# MainFile.net
KiCad netlist of a schematic drawn in Altium Designer
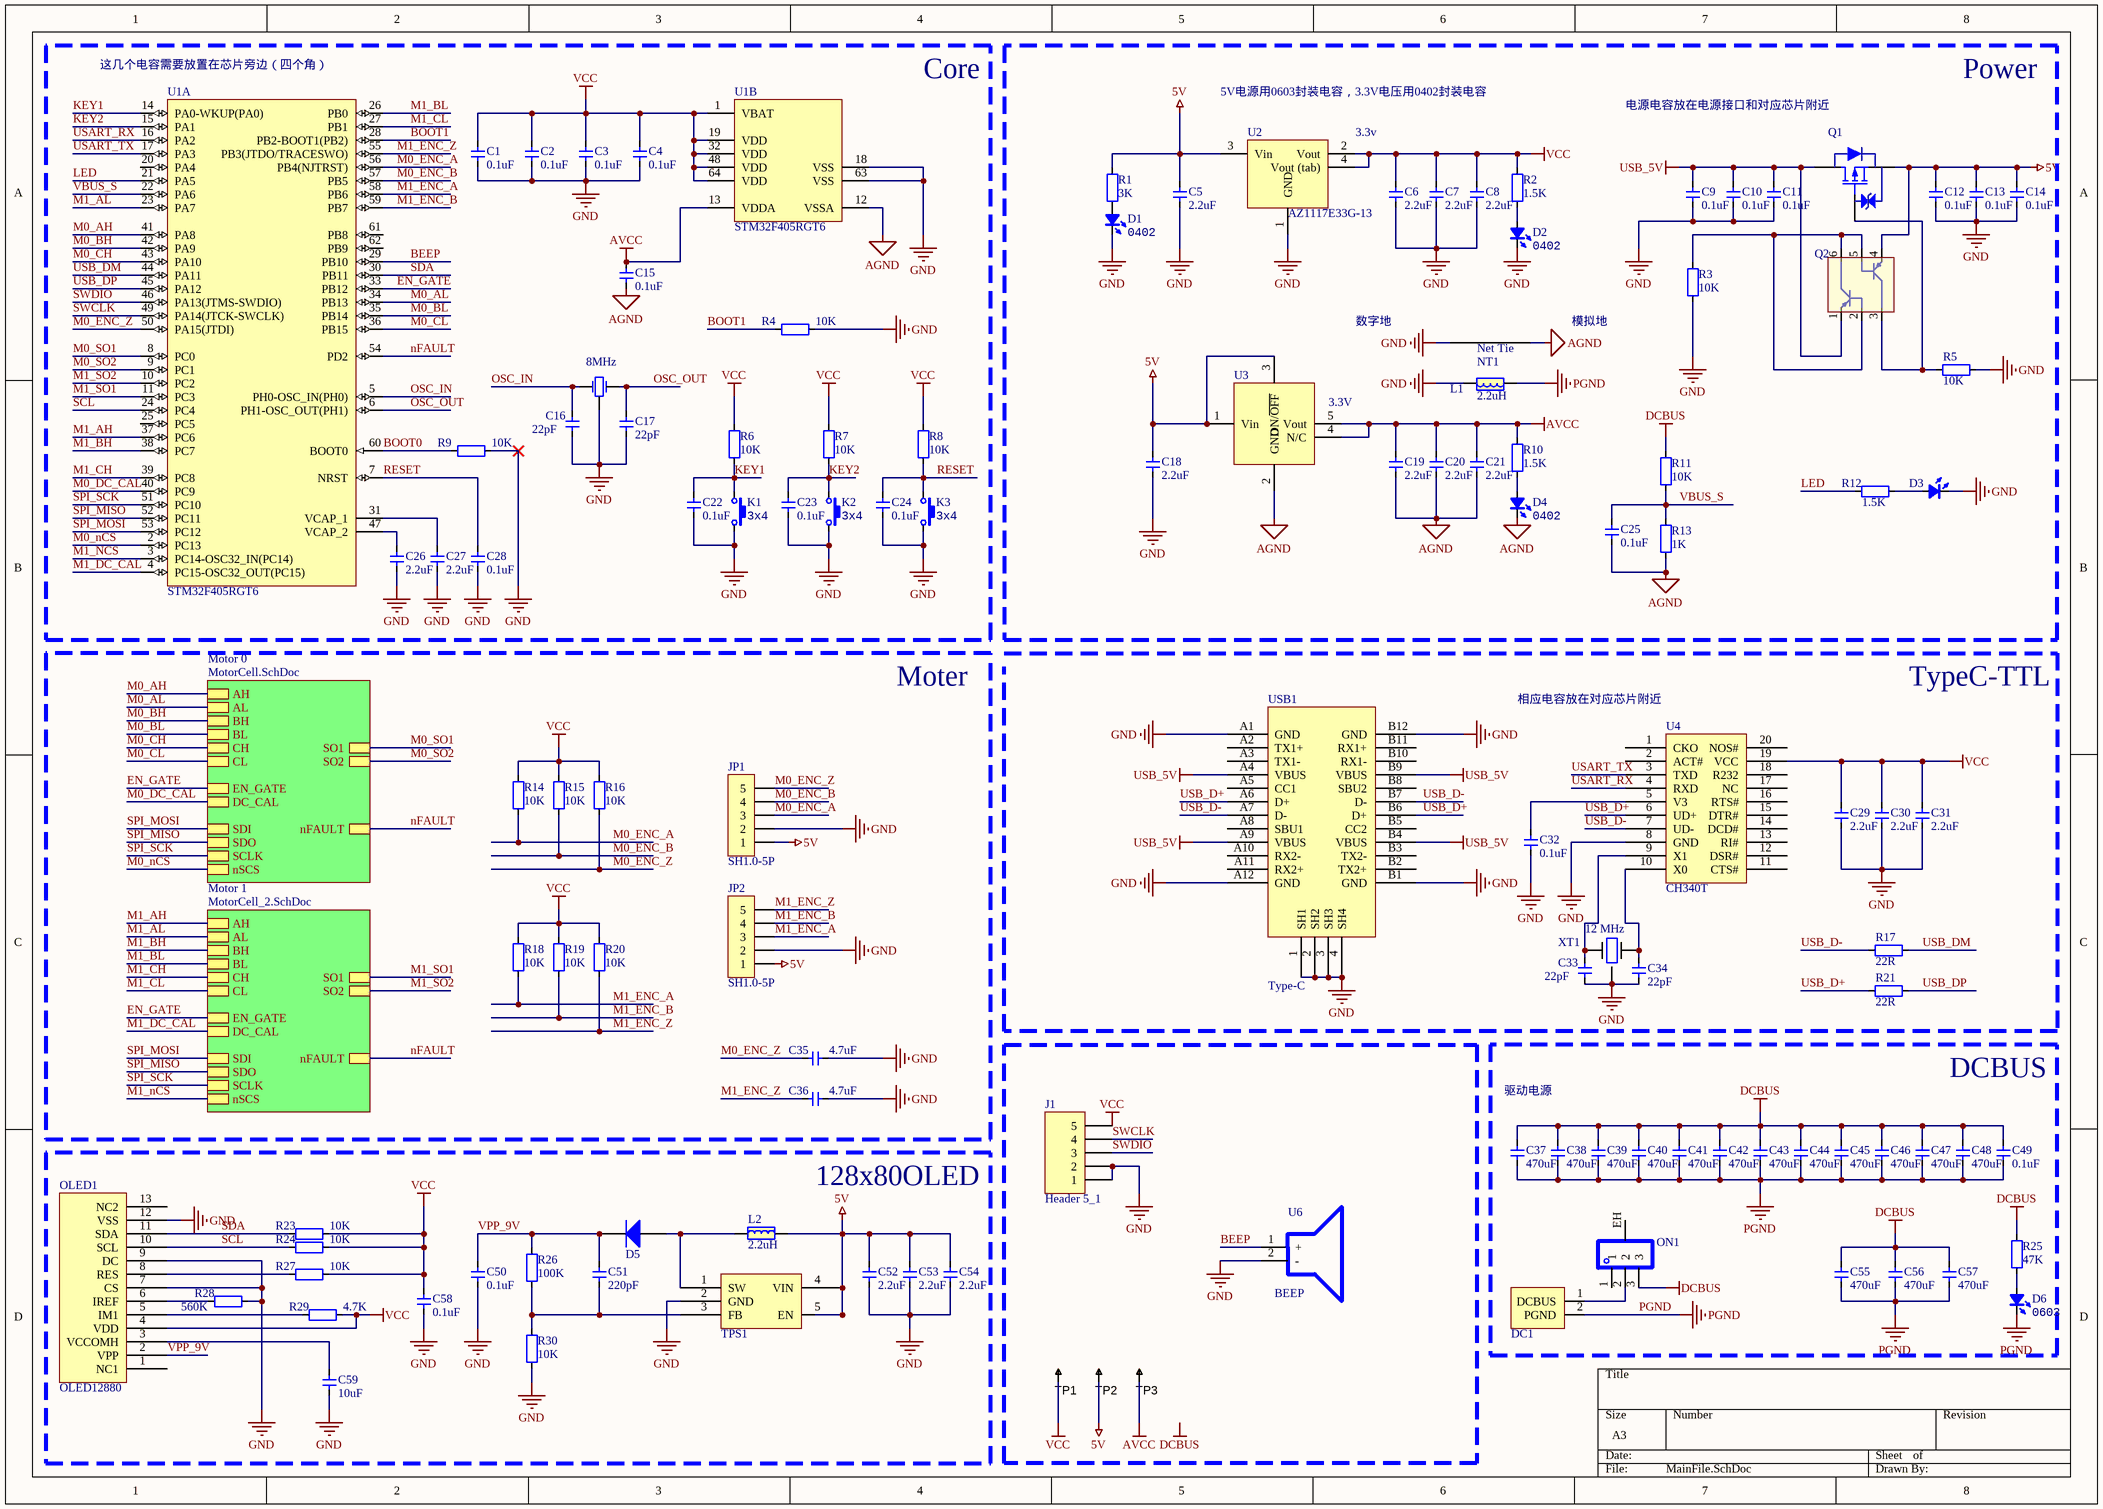
[diagram p0: MainFile.SchDoc]

(export (version "E")
  (design (tool "Eeschema 10.0.6"))
  (components
    (comp (ref "C1")
      (value "0.1uF")
      (footprint "CAP_0402")
      (description "Capacitor")
      (libsource (lib "VectorController") (part "电容-0402"))
    )
    (comp (ref "C2")
      (value "0.1uF")
      (footprint "CAP_0402")
      (description "Capacitor")
      (libsource (lib "VectorController") (part "电容-0402"))
    )
    (comp (ref "C3")
      (value "0.1uF")
      (footprint "CAP_0402")
      (description "Capacitor")
      (libsource (lib "VectorController") (part "电容-0402"))
    )
    (comp (ref "C4")
      (value "0.1uF")
      (footprint "CAP_0402")
      (description "Capacitor")
      (libsource (lib "VectorController") (part "电容-0402"))
    )
    (comp (ref "C5")
      (value "2.2uF")
      (footprint "CAP_0603")
      (description "Capacitor")
      (libsource (lib "Ctrl_FOC") (part "电容-0603"))
    )
    (comp (ref "C6")
      (value "2.2uF")
      (footprint "CAP_0402")
      (description "Capacitor")
      (libsource (lib "Ctrl_FOC") (part "电容-0402"))
    )
    (comp (ref "C7")
      (value "2.2uF")
      (footprint "CAP_0402")
      (description "Capacitor")
      (libsource (lib "Ctrl_FOC") (part "电容-0402"))
    )
    (comp (ref "C8")
      (value "2.2uF")
      (footprint "CAP_0402")
      (description "Capacitor")
      (libsource (lib "Ctrl_FOC") (part "电容-0402"))
    )
    (comp (ref "C9")
      (value "0.1uF")
      (footprint "CAP_0603")
      (description "Capacitor")
      (libsource (lib "Ctrl_FOC") (part "电容-0603"))
    )
    (comp (ref "C10")
      (value "0.1uF")
      (footprint "CAP_0603")
      (description "Capacitor")
      (libsource (lib "Ctrl_FOC") (part "电容-0603"))
    )
    (comp (ref "C11")
      (value "0.1uF")
      (footprint "CAP_0603")
      (description "Capacitor")
      (libsource (lib "Ctrl_FOC") (part "电容-0603"))
    )
    (comp (ref "C12")
      (value "0.1uF")
      (footprint "CAP_0603")
      (description "Capacitor")
      (libsource (lib "Ctrl_FOC") (part "电容-0603"))
    )
    (comp (ref "C13")
      (value "0.1uF")
      (footprint "CAP_0603")
      (description "Capacitor")
      (libsource (lib "Ctrl_FOC") (part "电容-0603"))
    )
    (comp (ref "C14")
      (value "0.1uF")
      (footprint "CAP_0603")
      (description "Capacitor")
      (libsource (lib "Ctrl_FOC") (part "电容-0603"))
    )
    (comp (ref "C15")
      (value "0.1uF")
      (footprint "CAP_0603")
      (description "Capacitor")
      (libsource (lib "Ctrl_FOC") (part "电容-0603"))
    )
    (comp (ref "C16")
      (value "22pF")
      (footprint "CAP_0402")
      (description "Capacitor")
      (libsource (lib "Ctrl_FOC") (part "电容-0402"))
    )
    (comp (ref "C17")
      (value "22pF")
      (footprint "CAP_0402")
      (description "Capacitor")
      (libsource (lib "Ctrl_FOC") (part "电容-0402"))
    )
    (comp (ref "C18")
      (value "2.2uF")
      (footprint "CAP_0603")
      (description "Capacitor")
      (libsource (lib "Ctrl_FOC") (part "电容-0603"))
    )
    (comp (ref "C19")
      (value "2.2uF")
      (footprint "CAP_0402")
      (description "Capacitor")
      (libsource (lib "Ctrl_FOC") (part "电容-0402"))
    )
    (comp (ref "C20")
      (value "2.2uF")
      (footprint "CAP_0402")
      (description "Capacitor")
      (libsource (lib "Ctrl_FOC") (part "电容-0402"))
    )
    (comp (ref "C21")
      (value "2.2uF")
      (footprint "CAP_0402")
      (description "Capacitor")
      (libsource (lib "Ctrl_FOC") (part "电容-0402"))
    )
    (comp (ref "C22")
      (value "0.1uF")
      (footprint "CAP_0402")
      (description "Capacitor")
      (libsource (lib "VectorController") (part "电容-0402"))
    )
    (comp (ref "C23")
      (value "0.1uF")
      (footprint "CAP_0402")
      (description "Capacitor")
      (libsource (lib "VectorController") (part "电容-0402"))
    )
    (comp (ref "C24")
      (value "0.1uF")
      (footprint "CAP_0402")
      (description "Capacitor")
      (libsource (lib "VectorController") (part "电容-0402"))
    )
    (comp (ref "C25")
      (value "0.1uF")
      (footprint "CAP_0603")
      (description "Capacitor")
      (libsource (lib "Ctrl_FOC") (part "电容-0603"))
    )
    (comp (ref "C26")
      (value "2.2uF")
      (footprint "CAP_0402")
      (description "Capacitor")
      (libsource (lib "Ctrl_FOC") (part "电容-0402"))
    )
    (comp (ref "C27")
      (value "2.2uF")
      (footprint "CAP_0402")
      (description "Capacitor")
      (libsource (lib "Ctrl_FOC") (part "电容-0402"))
    )
    (comp (ref "C28")
      (value "0.1uF")
      (footprint "CAP_0402")
      (description "Capacitor")
      (libsource (lib "Ctrl_FOC") (part "电容-0402"))
    )
    (comp (ref "C29")
      (value "2.2uF")
      (footprint "CAP_0603")
      (description "Capacitor")
      (libsource (lib "Ctrl_FOC") (part "电容-0603"))
    )
    (comp (ref "C30")
      (value "2.2uF")
      (footprint "CAP_0603")
      (description "Capacitor")
      (libsource (lib "Ctrl_FOC") (part "电容-0603"))
    )
    (comp (ref "C31")
      (value "2.2uF")
      (footprint "CAP_0603")
      (description "Capacitor")
      (libsource (lib "Ctrl_FOC") (part "电容-0603"))
    )
    (comp (ref "C32")
      (value "0.1uF")
      (footprint "CAP_0402")
      (description "Capacitor")
      (libsource (lib "Ctrl_FOC") (part "电容-0402"))
    )
    (comp (ref "C33")
      (value "22pF")
      (footprint "CAP_0402")
      (description "Capacitor")
      (libsource (lib "Ctrl_FOC") (part "电容-0402"))
    )
    (comp (ref "C34")
      (value "22pF")
      (footprint "CAP_0402")
      (description "Capacitor")
      (libsource (lib "Ctrl_FOC") (part "电容-0402"))
    )
    (comp (ref "C35")
      (value "4.7uF")
      (footprint "CAP_0402")
      (description "Capacitor")
      (libsource (lib "VectorController") (part "电容-0402"))
    )
    (comp (ref "C36")
      (value "4.7uF")
      (footprint "CAP_0402")
      (description "Capacitor")
      (libsource (lib "VectorController") (part "电容-0402"))
    )
    (comp (ref "C37")
      (value "470uF")
      (footprint "CAP_1206")
      (description "Capacitor")
      (libsource (lib "Ctrl_FOC") (part "电容-1206"))
    )
    (comp (ref "C38")
      (value "470uF")
      (footprint "CAP_1206")
      (description "Capacitor")
      (libsource (lib "Ctrl_FOC") (part "电容-1206"))
    )
    (comp (ref "C39")
      (value "470uF")
      (footprint "CAP_1206")
      (description "Capacitor")
      (libsource (lib "Ctrl_FOC") (part "电容-1206"))
    )
    (comp (ref "C40")
      (value "470uF")
      (footprint "CAP_1206")
      (description "Capacitor")
      (libsource (lib "Ctrl_FOC") (part "电容-1206"))
    )
    (comp (ref "C41")
      (value "470uF")
      (footprint "CAP_1206")
      (description "Capacitor")
      (libsource (lib "Ctrl_FOC") (part "电容-1206"))
    )
    (comp (ref "C42")
      (value "470uF")
      (footprint "CAP_1206")
      (description "Capacitor")
      (libsource (lib "Ctrl_FOC") (part "电容-1206"))
    )
    (comp (ref "C43")
      (value "470uF")
      (footprint "CAP_1206")
      (description "Capacitor")
      (libsource (lib "Ctrl_FOC") (part "电容-1206"))
    )
    (comp (ref "C44")
      (value "470uF")
      (footprint "CAP_1206")
      (description "Capacitor")
      (libsource (lib "Ctrl_FOC") (part "电容-1206"))
    )
    (comp (ref "C45")
      (value "470uF")
      (footprint "CAP_1206")
      (description "Capacitor")
      (libsource (lib "Ctrl_FOC") (part "电容-1206"))
    )
    (comp (ref "C46")
      (value "470uF")
      (footprint "CAP_1206")
      (description "Capacitor")
      (libsource (lib "Ctrl_FOC") (part "电容-1206"))
    )
    (comp (ref "C47")
      (value "470uF")
      (footprint "CAP_1206")
      (description "Capacitor")
      (libsource (lib "Ctrl_FOC") (part "电容-1206"))
    )
    (comp (ref "C48")
      (value "470uF")
      (footprint "CAP_1206")
      (description "Capacitor")
      (libsource (lib "Ctrl_FOC") (part "电容-1206"))
    )
    (comp (ref "C49")
      (value "0.1uF")
      (footprint "CAP_1206")
      (description "Capacitor")
      (libsource (lib "Ctrl_FOC") (part "电容-1206"))
    )
    (comp (ref "C50")
      (value "0.1uF")
      (footprint "CAP_0402")
      (description "Capacitor")
      (libsource (lib "VectorController") (part "电容-0402"))
    )
    (comp (ref "C51")
      (value "220pF")
      (footprint "CAP_0402")
      (description "Capacitor")
      (libsource (lib "VectorController") (part "电容-0402"))
    )
    (comp (ref "C52")
      (value "2.2uF")
      (footprint "CAP_0603")
      (description "Capacitor")
      (libsource (lib "Ctrl_FOC") (part "电容-0603"))
    )
    (comp (ref "C53")
      (value "2.2uF")
      (footprint "CAP_0603")
      (description "Capacitor")
      (libsource (lib "Ctrl_FOC") (part "电容-0603"))
    )
    (comp (ref "C54")
      (value "2.2uF")
      (footprint "CAP_0603")
      (description "Capacitor")
      (libsource (lib "Ctrl_FOC") (part "电容-0603"))
    )
    (comp (ref "C55")
      (value "470uF")
      (footprint "CAP_1206")
      (description "Capacitor")
      (libsource (lib "Ctrl_FOC") (part "电容-1206"))
    )
    (comp (ref "C56")
      (value "470uF")
      (footprint "CAP_1206")
      (description "Capacitor")
      (libsource (lib "Ctrl_FOC") (part "电容-1206"))
    )
    (comp (ref "C57")
      (value "470uF")
      (footprint "CAP_1206")
      (description "Capacitor")
      (libsource (lib "Ctrl_FOC") (part "电容-1206"))
    )
    (comp (ref "C58")
      (value "0.1uF")
      (footprint "CAP_0402")
      (description "Capacitor")
      (libsource (lib "VectorController") (part "电容-0402"))
    )
    (comp (ref "C59")
      (value "10uF")
      (footprint "CAP_0402")
      (description "Capacitor")
      (libsource (lib "VectorController") (part "电容-0402"))
    )
    (comp (ref "D1")
      (value "color?")
      (footprint "LED_0402_BLUE")
      (description "LED")
      (fields (field (name "TYPE") "0402"))
      (libsource (lib "Ctrl_FOC") (part "LED_0402"))
    )
    (comp (ref "D2")
      (value "color?")
      (footprint "LED_0402_BLUE")
      (description "LED")
      (fields (field (name "TYPE") "0402"))
      (libsource (lib "Ctrl_FOC") (part "LED_0402"))
    )
    (comp (ref "D3")
      (value "color?")
      (footprint "LED_0402_BLUE")
      (description "LED")
      (libsource (lib "Vibration") (part "LED_0402"))
    )
    (comp (ref "D4")
      (value "color?")
      (footprint "LED_0402_BLUE")
      (description "LED")
      (fields (field (name "TYPE") "0402"))
      (libsource (lib "Ctrl_FOC") (part "LED_0402"))
    )
    (comp (ref "D5")
      (value "二极管-5819W")
      (footprint "SOD-123")
      (description "40V")
      (libsource (lib "VectorController") (part "二极管-5819W"))
    )
    (comp (ref "D6")
      (value "color?")
      (footprint "LED_0603")
      (description "LED")
      (fields (field (name "TYPE") "0603"))
      (libsource (lib "Ctrl_FOC") (part "LED_0603"))
    )
    (comp (ref "DC1")
      (value "电源")
      (footprint "TX60电源")
      (description "12~24VDC电源")
      (libsource (lib "Ctrl_FOC") (part "电源"))
    )
    (comp (ref "J1")
      (value "Header 5_1")
      (footprint "单排弯插针5")
      (description "Header, 5-Pin")
      (fields (field (name "PUBLISHER") "Altium Limited"))
      (libsource (lib "VectorController") (part "Header 5_1"))
    )
    (comp (ref "JP1")
      (value "SH1.0-5P")
      (footprint "SH1.0-5P-L")
      (description "5P接插件")
      (libsource (lib "VectorController") (part "Header 5"))
    )
    (comp (ref "JP2")
      (value "SH1.0-5P")
      (footprint "SH1.0-5P-L")
      (description "5P接插件")
      (libsource (lib "VectorController") (part "Header 5"))
    )
    (comp (ref "K1")
      (value "3x4")
      (footprint "按键_3x4x2")
      (description "Button")
      (fields (field (name "Comment") "TACT 2P"))
      (libsource (lib "Ctrl_FOC") (part "ButtonTACT_3x4x2_180"))
    )
    (comp (ref "K2")
      (value "3x4")
      (footprint "按键_3x4x2")
      (description "Button")
      (fields (field (name "Comment") "TACT 2P"))
      (libsource (lib "Ctrl_FOC") (part "ButtonTACT_3x4x2_180"))
    )
    (comp (ref "K3")
      (value "3x4")
      (footprint "按键_3x4x2")
      (description "Button")
      (fields (field (name "Comment") "TACT 2P"))
      (libsource (lib "Ctrl_FOC") (part "ButtonTACT_3x4x2_180"))
    )
    (comp (ref "L1")
      (value "2.2uH")
      (footprint "2520-L")
      (description "磁珠")
      (libsource (lib "VectorController") (part "电感-0805"))
    )
    (comp (ref "L2")
      (value "2.2uH")
      (footprint "2520-L")
      (description "磁珠")
      (libsource (lib "") (part "电感-0805_1"))
    )
    (comp (ref "NT1") (value "2mm") (footprint "NetTie_2mm") (libsource (lib "Ctrl_FOC") (part "NetTie_2mm")))
    (comp (ref "OLED1")
      (value "OLED12880")
      (footprint "OLED12880")
      (description "12880寸OLED")
      (libsource (lib "VectorController") (part "OLED12880"))
    )
    (comp (ref "ON1") (value "电源开关") (footprint "电源开关") (libsource (lib "Ctrl_FOC") (part "电源开关")))
    (comp (ref "Q1")
      (value "AO3415A")
      (footprint "SOT23-3")
      (description "MOSFET")
      (fields (field (name "PUBLISHER") "Altium Limited"))
      (libsource (lib "Ctrl_FOC") (part "AO3415A"))
    )
    (comp (ref "Q2")
      (value "BCM856BS")
      (footprint "SOT363-6")
      (description "Transistor")
      (libsource (lib "Ctrl_FOC") (part "BCM856BS"))
    )
    (comp (ref "R1")
      (value "3K")
      (footprint "RES_0603")
      (description "Resistor")
      (libsource (lib "Ctrl_FOC") (part "电阻-0603"))
    )
    (comp (ref "R2")
      (value "1.5K")
      (footprint "RES_0402")
      (description "Resistor")
      (libsource (lib "") (part "电阻-0402_2"))
    )
    (comp (ref "R3")
      (value "10K")
      (footprint "RES_0603")
      (description "Resistor")
      (libsource (lib "") (part "电阻-0603_3"))
    )
    (comp (ref "R4")
      (value "10K")
      (footprint "RES_0402")
      (description "Resistor")
      (libsource (lib "Ctrl_FOC") (part "电阻-0402"))
    )
    (comp (ref "R5")
      (value "10K")
      (footprint "RES_0603")
      (description "Resistor")
      (libsource (lib "") (part "电阻-0603_1"))
    )
    (comp (ref "R6")
      (value "10K")
      (footprint "RES_0402")
      (description "Resistor")
      (libsource (lib "") (part "电阻-0402_1"))
    )
    (comp (ref "R7")
      (value "10K")
      (footprint "RES_0402")
      (description "Resistor")
      (libsource (lib "") (part "电阻-0402_1"))
    )
    (comp (ref "R8")
      (value "10K")
      (footprint "RES_0402")
      (description "Resistor")
      (libsource (lib "") (part "电阻-0402_1"))
    )
    (comp (ref "R9")
      (value "10K")
      (footprint "RES_0402")
      (description "Resistor")
      (libsource (lib "Ctrl_FOC") (part "电阻-0402"))
    )
    (comp (ref "R10")
      (value "1.5K")
      (footprint "RES_0402")
      (description "Resistor")
      (libsource (lib "") (part "电阻-0402_2"))
    )
    (comp (ref "R11")
      (value "10K")
      (footprint "RES_0603")
      (description "Resistor")
      (libsource (lib "Ctrl_FOC") (part "电阻-0603"))
    )
    (comp (ref "R12")
      (value "1.5K")
      (footprint "RES_0402")
      (description "Resistor")
      (libsource (lib "Vibration") (part "电阻-0402"))
    )
    (comp (ref "R13")
      (value "1K")
      (footprint "RES_0603")
      (description "Resistor")
      (libsource (lib "Ctrl_FOC") (part "电阻-0603"))
    )
    (comp (ref "R14")
      (value "10K")
      (footprint "RES_0603")
      (description "Resistor")
      (libsource (lib "Ctrl_FOC") (part "电阻-0603"))
    )
    (comp (ref "R15")
      (value "10K")
      (footprint "RES_0603")
      (description "Resistor")
      (libsource (lib "Ctrl_FOC") (part "电阻-0603"))
    )
    (comp (ref "R16")
      (value "10K")
      (footprint "RES_0603")
      (description "Resistor")
      (libsource (lib "Ctrl_FOC") (part "电阻-0603"))
    )
    (comp (ref "R17")
      (value "22R")
      (footprint "RES_0603")
      (description "Resistor")
      (libsource (lib "") (part "电阻-0603_2"))
    )
    (comp (ref "R18")
      (value "10K")
      (footprint "RES_0603")
      (description "Resistor")
      (libsource (lib "Ctrl_FOC") (part "电阻-0603"))
    )
    (comp (ref "R19")
      (value "10K")
      (footprint "RES_0603")
      (description "Resistor")
      (libsource (lib "Ctrl_FOC") (part "电阻-0603"))
    )
    (comp (ref "R20")
      (value "10K")
      (footprint "RES_0603")
      (description "Resistor")
      (libsource (lib "Ctrl_FOC") (part "电阻-0603"))
    )
    (comp (ref "R21")
      (value "22R")
      (footprint "RES_0603")
      (description "Resistor")
      (libsource (lib "") (part "电阻-0603_2"))
    )
    (comp (ref "R23")
      (value "10K")
      (footprint "RES_0402")
      (description "Resistor")
      (libsource (lib "VectorController") (part "电阻-0402"))
    )
    (comp (ref "R24")
      (value "10K")
      (footprint "RES_0402")
      (description "Resistor")
      (libsource (lib "VectorController") (part "电阻-0402"))
    )
    (comp (ref "R25")
      (value "47K")
      (footprint "RES_0603")
      (description "Resistor")
      (libsource (lib "Ctrl_FOC") (part "电阻-0603"))
    )
    (comp (ref "R26")
      (value "100K")
      (footprint "RES_0402")
      (description "Resistor")
      (libsource (lib "") (part "电阻-0402_1"))
    )
    (comp (ref "R27")
      (value "10K")
      (footprint "RES_0402")
      (description "Resistor")
      (libsource (lib "VectorController") (part "电阻-0402"))
    )
    (comp (ref "R28")
      (value "560K")
      (footprint "RES_0402")
      (description "Resistor")
      (libsource (lib "VectorController") (part "电阻-0402"))
    )
    (comp (ref "R29")
      (value "4.7K")
      (footprint "RES_0402")
      (description "Resistor")
      (libsource (lib "VectorController") (part "电阻-0402"))
    )
    (comp (ref "R30")
      (value "10K")
      (footprint "RES_0402")
      (description "Resistor")
      (libsource (lib "") (part "电阻-0402_1"))
    )
    (comp (ref "TP1")
      (value "TESTPOINT")
      (footprint "TP-R30")
      (description "SMD test pin")
      (libsource (lib "Ctrl_FOC") (part "TESTPOINT"))
    )
    (comp (ref "TP2")
      (value "TESTPOINT")
      (footprint "TP-R30")
      (description "SMD test pin")
      (libsource (lib "Ctrl_FOC") (part "TESTPOINT"))
    )
    (comp (ref "TP3")
      (value "TESTPOINT")
      (footprint "TP-R30")
      (description "SMD test pin")
      (libsource (lib "Ctrl_FOC") (part "TESTPOINT"))
    )
    (comp (ref "TPS1")
      (value "TPS61040DBV")
      (footprint "SOT23-5")
      (libsource (lib "VectorController") (part "TPS61040DBV"))
    )
    (comp (ref "U1")
      (value "STM32F405RGT6")
      (footprint "主控芯片LQFP64-10*10")
      (fields (field (name "MANUFACTURER") "STMicroelectronics"))
      (libsource (lib "Ctrl_FOC") (part "STM32F405RGT6"))
    )
    (comp (ref "U2")
      (value "AZ1117E33G-13")
      (footprint "SOT223")
      (description "IC, LDO, REG, 3.3V, SOT223")
      (fields (field (name "ALTIUM_VALUE") "3.3v"))
      (libsource (lib "Ctrl_FOC") (part "AZ1117E33G-13"))
    )
    (comp (ref "U3")
      (value "3.3V")
      (footprint "SOT23-5")
      (description "IC REG LDO 3.3V 0.25A SOT23-5")
      (fields (field (name "MANUFACTURER") "Texas Instruments"))
      (libsource (lib "Ctrl_FOC") (part "LP5907MFX-3.3/NOPB"))
    )
    (comp (ref "U4")
      (value "CH340T")
      (footprint "SSOP-20")
      (description "Port")
      (libsource (lib "Ctrl_FOC") (part "CH340T"))
    )
    (comp (ref "U6") (value "BEEP") (footprint "BEEP") (libsource (lib "Ctrl_FOC") (part "BEEP")))
    (comp (ref "USB1")
      (value "Type-C")
      (footprint "Type-C-TOP")
      (libsource (lib "Ctrl_FOC") (part "USB-Type-C-TOP"))
    )
    (comp (ref "X1") (value "8MHz") (footprint "XTAL3215") (libsource (lib "MiniFly ") (part "XTAL-3215")))
    (comp (ref "XT1")
      (value "12 MHz")
      (footprint "DFN220P320X110-4N")
      (description "Crystal 8MHz ±10ppm 10pF 200 Ohm -10°C ~ 60°C Surface Mount 4-SMD, No Lead (DFN, LCC)")
      (fields
        (field (name "MANUFACTURER") "Abracon LLC")
        (field (name "MANUFACTURER PART NUMBER") "ABM3B-8.000MHZ-10-1-U-T")
      )
      (libsource (lib "Ctrl_FOC") (part "ABM3B-8.000MHZ-10-1-U-T"))
    )
  )
  (nets
    (net (code "1") (name "/BEEP") (class "Default")
      (node (ref "U1") (pin "29") (pinfunction "PB10_29") (pintype "bidirectional"))
      (node (ref "U6") (pin "1") (pinfunction "+_1") (pintype "passive"))
    )
    (net (code "2") (name "/BOOT0") (class "Default")
      (node (ref "R9") (pin "2") (pinfunction "2_2") (pintype "passive"))
      (node (ref "U1") (pin "60") (pinfunction "BOOT0_60") (pintype "input"))
    )
    (net (code "3") (name "/BOOT1") (class "Default")
      (node (ref "R4") (pin "2") (pinfunction "2_2") (pintype "passive"))
      (node (ref "U1") (pin "28") (pinfunction "PB2-BOOT1(PB2)_28") (pintype "bidirectional"))
    )
    (net (code "4") (name "/EN_GATE") (class "Default")
      (node (ref "U1") (pin "33") (pinfunction "PB12_33") (pintype "bidirectional"))
    )
    (net (code "5") (name "/KEY1") (class "Default")
      (node (ref "C22") (pin "2") (pinfunction "2_2") (pintype "passive"))
      (node (ref "K1") (pin "1") (pinfunction "1_1") (pintype "passive"))
      (node (ref "R6") (pin "2") (pinfunction "2_2") (pintype "passive"))
      (node (ref "U1") (pin "14") (pinfunction "PA0-WKUP(PA0)_14") (pintype "bidirectional"))
    )
    (net (code "6") (name "/KEY2") (class "Default")
      (node (ref "C23") (pin "2") (pinfunction "2_2") (pintype "passive"))
      (node (ref "K2") (pin "1") (pinfunction "1_1") (pintype "passive"))
      (node (ref "R7") (pin "2") (pinfunction "2_2") (pintype "passive"))
      (node (ref "U1") (pin "15") (pinfunction "PA1_15") (pintype "bidirectional"))
    )
    (net (code "7") (name "/LED") (class "Default")
      (node (ref "R12") (pin "1") (pinfunction "1_1") (pintype "passive"))
      (node (ref "U1") (pin "21") (pinfunction "PA5_21") (pintype "bidirectional"))
    )
    (net (code "8") (name "/M0_AH") (class "Default")
      (node (ref "U1") (pin "41") (pinfunction "PA8_41") (pintype "bidirectional"))
    )
    (net (code "9") (name "/M0_AL") (class "Default")
      (node (ref "U1") (pin "34") (pinfunction "PB13_34") (pintype "bidirectional"))
    )
    (net (code "10") (name "/M0_BH") (class "Default")
      (node (ref "U1") (pin "42") (pinfunction "PA9_42") (pintype "bidirectional"))
    )
    (net (code "11") (name "/M0_BL") (class "Default")
      (node (ref "U1") (pin "35") (pinfunction "PB14_35") (pintype "bidirectional"))
    )
    (net (code "12") (name "/M0_CH") (class "Default")
      (node (ref "U1") (pin "43") (pinfunction "PA10_43") (pintype "bidirectional"))
    )
    (net (code "13") (name "/M0_CL") (class "Default")
      (node (ref "U1") (pin "36") (pinfunction "PB15_36") (pintype "bidirectional"))
    )
    (net (code "14") (name "/M0_DC_CAL") (class "Default")
      (node (ref "U1") (pin "40") (pinfunction "PC9_40") (pintype "bidirectional"))
    )
    (net (code "15") (name "/M0_ENC_A") (class "Default")
      (node (ref "JP1") (pin "3") (pinfunction "3_3") (pintype "passive"))
      (node (ref "R14") (pin "1") (pinfunction "1_1") (pintype "passive"))
      (node (ref "U1") (pin "56") (pinfunction "PB4(NJTRST)_56") (pintype "bidirectional"))
    )
    (net (code "16") (name "/M0_ENC_B") (class "Default")
      (node (ref "JP1") (pin "4") (pinfunction "4_4") (pintype "passive"))
      (node (ref "R15") (pin "1") (pinfunction "1_1") (pintype "passive"))
      (node (ref "U1") (pin "57") (pinfunction "PB5_57") (pintype "bidirectional"))
    )
    (net (code "17") (name "/M0_ENC_Z") (class "Default")
      (node (ref "C35") (pin "2") (pinfunction "2_2") (pintype "passive"))
      (node (ref "JP1") (pin "5") (pinfunction "5_5") (pintype "passive"))
      (node (ref "R16") (pin "1") (pinfunction "1_1") (pintype "passive"))
      (node (ref "U1") (pin "50") (pinfunction "PA15(JTDI)_50") (pintype "bidirectional"))
    )
    (net (code "18") (name "/M0_SO1") (class "Default")
      (node (ref "U1") (pin "8") (pinfunction "PC0_8") (pintype "bidirectional"))
    )
    (net (code "19") (name "/M0_SO2") (class "Default")
      (node (ref "U1") (pin "9") (pinfunction "PC1_9") (pintype "bidirectional"))
    )
    (net (code "20") (name "/M0_nCS") (class "Default")
      (node (ref "U1") (pin "2") (pinfunction "PC13_2") (pintype "bidirectional"))
    )
    (net (code "21") (name "/M1_AH") (class "Default")
      (node (ref "U1") (pin "37") (pinfunction "PC6_37") (pintype "bidirectional"))
    )
    (net (code "22") (name "/M1_AL") (class "Default")
      (node (ref "U1") (pin "23") (pinfunction "PA7_23") (pintype "bidirectional"))
    )
    (net (code "23") (name "/M1_BH") (class "Default")
      (node (ref "U1") (pin "38") (pinfunction "PC7_38") (pintype "bidirectional"))
    )
    (net (code "24") (name "/M1_BL") (class "Default")
      (node (ref "U1") (pin "26") (pinfunction "PB0_26") (pintype "bidirectional"))
    )
    (net (code "25") (name "/M1_CH") (class "Default")
      (node (ref "U1") (pin "39") (pinfunction "PC8_39") (pintype "bidirectional"))
    )
    (net (code "26") (name "/M1_CL") (class "Default")
      (node (ref "U1") (pin "27") (pinfunction "PB1_27") (pintype "bidirectional"))
    )
    (net (code "27") (name "/M1_DC_CAL") (class "Default")
      (node (ref "U1") (pin "4") (pinfunction "PC15-OSC32_OUT(PC15)_4") (pintype "bidirectional"))
    )
    (net (code "28") (name "/M1_ENC_A") (class "Default")
      (node (ref "JP2") (pin "3") (pinfunction "3_3") (pintype "passive"))
      (node (ref "R18") (pin "1") (pinfunction "1_1") (pintype "passive"))
      (node (ref "U1") (pin "58") (pinfunction "PB6_58") (pintype "bidirectional"))
    )
    (net (code "29") (name "/M1_ENC_B") (class "Default")
      (node (ref "JP2") (pin "4") (pinfunction "4_4") (pintype "passive"))
      (node (ref "R19") (pin "1") (pinfunction "1_1") (pintype "passive"))
      (node (ref "U1") (pin "59") (pinfunction "PB7_59") (pintype "bidirectional"))
    )
    (net (code "30") (name "/M1_ENC_Z") (class "Default")
      (node (ref "C36") (pin "2") (pinfunction "2_2") (pintype "passive"))
      (node (ref "JP2") (pin "5") (pinfunction "5_5") (pintype "passive"))
      (node (ref "R20") (pin "1") (pinfunction "1_1") (pintype "passive"))
      (node (ref "U1") (pin "55") (pinfunction "PB3(JTDO/TRACESWO)_55") (pintype "bidirectional"))
    )
    (net (code "31") (name "/M1_NCS") (class "Default")
      (node (ref "U1") (pin "3") (pinfunction "PC14-OSC32_IN(PC14)_3") (pintype "bidirectional"))
    )
    (net (code "32") (name "/M1_SO1") (class "Default")
      (node (ref "U1") (pin "11") (pinfunction "PC3_11") (pintype "bidirectional"))
    )
    (net (code "33") (name "/M1_SO2") (class "Default")
      (node (ref "U1") (pin "10") (pinfunction "PC2_10") (pintype "bidirectional"))
    )
    (net (code "35") (name "/OSC_IN") (class "Default")
      (node (ref "C16") (pin "2") (pinfunction "2_2") (pintype "passive"))
      (node (ref "U1") (pin "5") (pinfunction "PH0-OSC_IN(PH0)_5") (pintype "bidirectional"))
      (node (ref "X1") (pin "1") (pinfunction "OSC1_1") (pintype "passive"))
    )
    (net (code "36") (name "/OSC_OUT") (class "Default")
      (node (ref "C17") (pin "2") (pinfunction "2_2") (pintype "passive"))
      (node (ref "U1") (pin "6") (pinfunction "PH1-OSC_OUT(PH1)_6") (pintype "bidirectional"))
      (node (ref "X1") (pin "3") (pinfunction "OSC2_3") (pintype "passive"))
    )
    (net (code "37") (name "/RESET") (class "Default")
      (node (ref "C24") (pin "2") (pinfunction "2_2") (pintype "passive"))
      (node (ref "C28") (pin "1") (pinfunction "1_1") (pintype "passive"))
      (node (ref "K3") (pin "1") (pinfunction "1_1") (pintype "passive"))
      (node (ref "R8") (pin "2") (pinfunction "2_2") (pintype "passive"))
      (node (ref "U1") (pin "7") (pinfunction "NRST_7") (pintype "bidirectional"))
    )
    (net (code "38") (name "/SCL") (class "Default")
      (node (ref "OLED1") (pin "10") (pinfunction "SCL_10") (pintype "passive"))
      (node (ref "R24") (pin "1") (pinfunction "1_1") (pintype "passive"))
      (node (ref "U1") (pin "24") (pinfunction "PC4_24") (pintype "bidirectional"))
    )
    (net (code "39") (name "/SDA") (class "Default")
      (node (ref "OLED1") (pin "11") (pinfunction "SDA_11") (pintype "passive"))
      (node (ref "R23") (pin "1") (pinfunction "1_1") (pintype "passive"))
      (node (ref "U1") (pin "30") (pinfunction "PB11_30") (pintype "bidirectional"))
    )
    (net (code "40") (name "/SPI_MISO") (class "Default")
      (node (ref "U1") (pin "52") (pinfunction "PC11_52") (pintype "bidirectional"))
    )
    (net (code "41") (name "/SPI_MOSI") (class "Default")
      (node (ref "U1") (pin "53") (pinfunction "PC12_53") (pintype "bidirectional"))
    )
    (net (code "42") (name "/SPI_SCK") (class "Default")
      (node (ref "U1") (pin "51") (pinfunction "PC10_51") (pintype "bidirectional"))
    )
    (net (code "43") (name "/SWCLK") (class "Default")
      (node (ref "J1") (pin "4") (pinfunction "4_4") (pintype "passive"))
      (node (ref "U1") (pin "49") (pinfunction "PA14(JTCK-SWCLK)_49") (pintype "bidirectional"))
    )
    (net (code "44") (name "/SWDIO") (class "Default")
      (node (ref "J1") (pin "3") (pinfunction "3_3") (pintype "passive"))
      (node (ref "U1") (pin "46") (pinfunction "PA13(JTMS-SWDIO)_46") (pintype "bidirectional"))
    )
    (net (code "45") (name "/USART_RX") (class "Default")
      (node (ref "U1") (pin "16") (pinfunction "PA2_16") (pintype "bidirectional"))
      (node (ref "U4") (pin "4") (pinfunction "RXD_4") (pintype "passive"))
    )
    (net (code "46") (name "/USART_TX") (class "Default")
      (node (ref "U1") (pin "17") (pinfunction "PA3_17") (pintype "bidirectional"))
      (node (ref "U4") (pin "3") (pinfunction "TXD_3") (pintype "passive"))
    )
    (net (code "47") (name "/USB_D+") (class "Default")
      (node (ref "R21") (pin "1") (pinfunction "1_1") (pintype "passive"))
      (node (ref "U4") (pin "6") (pinfunction "UD+_6") (pintype "passive"))
      (node (ref "USB1") (pin "A6") (pinfunction "D+_A6") (pintype "passive"))
      (node (ref "USB1") (pin "B6") (pinfunction "D+_B6") (pintype "passive"))
    )
    (net (code "48") (name "/USB_D-") (class "Default")
      (node (ref "R17") (pin "1") (pinfunction "1_1") (pintype "passive"))
      (node (ref "U4") (pin "7") (pinfunction "UD-_7") (pintype "passive"))
      (node (ref "USB1") (pin "A7") (pinfunction "D-_A7") (pintype "passive"))
      (node (ref "USB1") (pin "B7") (pinfunction "D-_B7") (pintype "passive"))
    )
    (net (code "49") (name "/USB_DM") (class "Default")
      (node (ref "R17") (pin "2") (pinfunction "2_2") (pintype "passive"))
      (node (ref "U1") (pin "44") (pinfunction "PA11_44") (pintype "bidirectional"))
    )
    (net (code "50") (name "/USB_DP") (class "Default")
      (node (ref "R21") (pin "2") (pinfunction "2_2") (pintype "passive"))
      (node (ref "U1") (pin "45") (pinfunction "PA12_45") (pintype "bidirectional"))
    )
    (net (code "51") (name "/VBUS_S") (class "Default")
      (node (ref "C25") (pin "2") (pinfunction "2_2") (pintype "passive"))
      (node (ref "R11") (pin "1") (pinfunction "1_1") (pintype "passive"))
      (node (ref "R13") (pin "2") (pinfunction "2_2") (pintype "passive"))
      (node (ref "U1") (pin "22") (pinfunction "PA6_22") (pintype "bidirectional"))
    )
    (net (code "52") (name "/VPP_9V") (class "Default")
      (node (ref "C50") (pin "2") (pinfunction "2_2") (pintype "passive"))
      (node (ref "C51") (pin "2") (pinfunction "2_2") (pintype "passive"))
      (node (ref "D5") (pin "2") (pinfunction "K_2") (pintype "passive"))
      (node (ref "OLED1") (pin "2") (pinfunction "VPP_2") (pintype "passive"))
      (node (ref "R26") (pin "2") (pinfunction "2_2") (pintype "passive"))
    )
    (net (code "53") (name "/nFAULT") (class "Default")
      (node (ref "U1") (pin "54") (pinfunction "PD2_54") (pintype "bidirectional"))
    )
    (net (code "54") (name "5V") (class "Default")
      (node (ref "C12") (pin "2") (pinfunction "2_2") (pintype "passive"))
      (node (ref "C13") (pin "2") (pinfunction "2_2") (pintype "passive"))
      (node (ref "C14") (pin "2") (pinfunction "2_2") (pintype "passive"))
      (node (ref "C18") (pin "2") (pinfunction "2_2") (pintype "passive"))
      (node (ref "C5") (pin "2") (pinfunction "2_2") (pintype "passive"))
      (node (ref "C52") (pin "2") (pinfunction "2_2") (pintype "passive"))
      (node (ref "C53") (pin "2") (pinfunction "2_2") (pintype "passive"))
      (node (ref "C54") (pin "2") (pinfunction "2_2") (pintype "passive"))
      (node (ref "JP1") (pin "1") (pinfunction "1_1") (pintype "passive"))
      (node (ref "JP2") (pin "1") (pinfunction "1_1") (pintype "passive"))
      (node (ref "L2") (pin "2") (pinfunction "2_2") (pintype "passive"))
      (node (ref "Q1") (pin "2") (pinfunction "S_2") (pintype "passive"))
      (node (ref "Q2") (pin "4") (pintype "passive"))
      (node (ref "R1") (pin "2") (pinfunction "2_2") (pintype "passive"))
      (node (ref "TP2") (pin "1") (pintype "passive"))
      (node (ref "TPS1") (pin "4") (pinfunction "VIN_4") (pintype "passive"))
      (node (ref "TPS1") (pin "5") (pinfunction "EN_5") (pintype "passive"))
      (node (ref "U2") (pin "3") (pinfunction "Vin_3") (pintype "passive"))
      (node (ref "U3") (pin "1") (pinfunction "Vin_1") (pintype "passive"))
      (node (ref "U3") (pin "3") (pinfunction "ON/~{OFF}_3") (pintype "passive"))
    )
    (net (code "55") (name "AGND") (class "Default")
      (node (ref "C15") (pin "1") (pinfunction "1_1") (pintype "passive"))
      (node (ref "C19") (pin "1") (pinfunction "1_1") (pintype "passive"))
      (node (ref "C20") (pin "1") (pinfunction "1_1") (pintype "passive"))
      (node (ref "C21") (pin "1") (pinfunction "1_1") (pintype "passive"))
      (node (ref "C25") (pin "1") (pinfunction "1_1") (pintype "passive"))
      (node (ref "D4") (pin "2") (pinfunction "K_2") (pintype "passive"))
      (node (ref "NT1") (pin "2") (pintype "passive"))
      (node (ref "R13") (pin "1") (pinfunction "1_1") (pintype "passive"))
      (node (ref "U1") (pin "12") (pinfunction "VSSA_12") (pintype "power_in"))
      (node (ref "U3") (pin "2") (pinfunction "GND_2") (pintype "passive"))
    )
    (net (code "56") (name "AVCC") (class "Default")
      (node (ref "C15") (pin "2") (pinfunction "2_2") (pintype "passive"))
      (node (ref "C19") (pin "2") (pinfunction "2_2") (pintype "passive"))
      (node (ref "C20") (pin "2") (pinfunction "2_2") (pintype "passive"))
      (node (ref "C21") (pin "2") (pinfunction "2_2") (pintype "passive"))
      (node (ref "R10") (pin "2") (pinfunction "2_2") (pintype "passive"))
      (node (ref "TP3") (pin "1") (pintype "passive"))
      (node (ref "U1") (pin "13") (pinfunction "VDDA_13") (pintype "power_in"))
      (node (ref "U3") (pin "4") (pinfunction "N/C_4") (pintype "passive"))
      (node (ref "U3") (pin "5") (pinfunction "Vout_5") (pintype "passive"))
    )
    (net (code "57") (name "DCBUS") (class "Default")
      (node (ref "C37") (pin "2") (pinfunction "2_2") (pintype "passive"))
      (node (ref "C38") (pin "2") (pinfunction "2_2") (pintype "passive"))
      (node (ref "C39") (pin "2") (pinfunction "2_2") (pintype "passive"))
      (node (ref "C40") (pin "2") (pinfunction "2_2") (pintype "passive"))
      (node (ref "C41") (pin "2") (pinfunction "2_2") (pintype "passive"))
      (node (ref "C42") (pin "2") (pinfunction "2_2") (pintype "passive"))
      (node (ref "C43") (pin "2") (pinfunction "2_2") (pintype "passive"))
      (node (ref "C44") (pin "2") (pinfunction "2_2") (pintype "passive"))
      (node (ref "C45") (pin "2") (pinfunction "2_2") (pintype "passive"))
      (node (ref "C46") (pin "2") (pinfunction "2_2") (pintype "passive"))
      (node (ref "C47") (pin "2") (pinfunction "2_2") (pintype "passive"))
      (node (ref "C48") (pin "2") (pinfunction "2_2") (pintype "passive"))
      (node (ref "C49") (pin "2") (pinfunction "2_2") (pintype "passive"))
      (node (ref "C55") (pin "2") (pinfunction "2_2") (pintype "passive"))
      (node (ref "C56") (pin "2") (pinfunction "2_2") (pintype "passive"))
      (node (ref "C57") (pin "2") (pinfunction "2_2") (pintype "passive"))
      (node (ref "ON1") (pin "3") (pinfunction "3_3") (pintype "passive"))
      (node (ref "R11") (pin "2") (pinfunction "2_2") (pintype "passive"))
      (node (ref "R25") (pin "2") (pinfunction "2_2") (pintype "passive"))
    )
    (net (code "58") (name "GND") (class "Default")
      (node (ref "C1") (pin "1") (pinfunction "1_1") (pintype "passive"))
      (node (ref "C10") (pin "1") (pinfunction "1_1") (pintype "passive"))
      (node (ref "C11") (pin "1") (pinfunction "1_1") (pintype "passive"))
      (node (ref "C12") (pin "1") (pinfunction "1_1") (pintype "passive"))
      (node (ref "C13") (pin "1") (pinfunction "1_1") (pintype "passive"))
      (node (ref "C14") (pin "1") (pinfunction "1_1") (pintype "passive"))
      (node (ref "C16") (pin "1") (pinfunction "1_1") (pintype "passive"))
      (node (ref "C17") (pin "1") (pinfunction "1_1") (pintype "passive"))
      (node (ref "C18") (pin "1") (pinfunction "1_1") (pintype "passive"))
      (node (ref "C2") (pin "1") (pinfunction "1_1") (pintype "passive"))
      (node (ref "C22") (pin "1") (pinfunction "1_1") (pintype "passive"))
      (node (ref "C23") (pin "1") (pinfunction "1_1") (pintype "passive"))
      (node (ref "C24") (pin "1") (pinfunction "1_1") (pintype "passive"))
      (node (ref "C26") (pin "1") (pinfunction "1_1") (pintype "passive"))
      (node (ref "C27") (pin "1") (pinfunction "1_1") (pintype "passive"))
      (node (ref "C28") (pin "2") (pinfunction "2_2") (pintype "passive"))
      (node (ref "C29") (pin "1") (pinfunction "1_1") (pintype "passive"))
      (node (ref "C3") (pin "1") (pinfunction "1_1") (pintype "passive"))
      (node (ref "C30") (pin "1") (pinfunction "1_1") (pintype "passive"))
      (node (ref "C31") (pin "1") (pinfunction "1_1") (pintype "passive"))
      (node (ref "C32") (pin "1") (pinfunction "1_1") (pintype "passive"))
      (node (ref "C33") (pin "1") (pinfunction "1_1") (pintype "passive"))
      (node (ref "C34") (pin "1") (pinfunction "1_1") (pintype "passive"))
      (node (ref "C35") (pin "1") (pinfunction "1_1") (pintype "passive"))
      (node (ref "C36") (pin "1") (pinfunction "1_1") (pintype "passive"))
      (node (ref "C4") (pin "1") (pinfunction "1_1") (pintype "passive"))
      (node (ref "C5") (pin "1") (pinfunction "1_1") (pintype "passive"))
      (node (ref "C50") (pin "1") (pinfunction "1_1") (pintype "passive"))
      (node (ref "C52") (pin "1") (pinfunction "1_1") (pintype "passive"))
      (node (ref "C53") (pin "1") (pinfunction "1_1") (pintype "passive"))
      (node (ref "C54") (pin "1") (pinfunction "1_1") (pintype "passive"))
      (node (ref "C58") (pin "1") (pinfunction "1_1") (pintype "passive"))
      (node (ref "C59") (pin "1") (pinfunction "1_1") (pintype "passive"))
      (node (ref "C6") (pin "1") (pinfunction "1_1") (pintype "passive"))
      (node (ref "C7") (pin "1") (pinfunction "1_1") (pintype "passive"))
      (node (ref "C8") (pin "1") (pinfunction "1_1") (pintype "passive"))
      (node (ref "C9") (pin "1") (pinfunction "1_1") (pintype "passive"))
      (node (ref "D1") (pin "2") (pinfunction "K_2") (pintype "passive"))
      (node (ref "D2") (pin "2") (pinfunction "K_2") (pintype "passive"))
      (node (ref "D3") (pin "2") (pinfunction "K_2") (pintype "passive"))
      (node (ref "J1") (pin "1") (pinfunction "1_1") (pintype "passive"))
      (node (ref "J1") (pin "2") (pinfunction "2_2") (pintype "passive"))
      (node (ref "JP1") (pin "2") (pinfunction "2_2") (pintype "passive"))
      (node (ref "JP2") (pin "2") (pinfunction "2_2") (pintype "passive"))
      (node (ref "K1") (pin "2") (pinfunction "2_2") (pintype "passive"))
      (node (ref "K2") (pin "2") (pinfunction "2_2") (pintype "passive"))
      (node (ref "K3") (pin "2") (pinfunction "2_2") (pintype "passive"))
      (node (ref "L1") (pin "2") (pinfunction "2_2") (pintype "passive"))
      (node (ref "NT1") (pin "1") (pintype "passive"))
      (node (ref "OLED1") (pin "12") (pinfunction "VSS_12") (pintype "passive"))
      (node (ref "OLED1") (pin "7") (pinfunction "CS_7") (pintype "passive"))
      (node (ref "OLED1") (pin "9") (pinfunction "DC_9") (pintype "passive"))
      (node (ref "R28") (pin "2") (pinfunction "2_2") (pintype "passive"))
      (node (ref "R3") (pin "2") (pinfunction "2_2") (pintype "passive"))
      (node (ref "R30") (pin "1") (pinfunction "1_1") (pintype "passive"))
      (node (ref "R4") (pin "1") (pinfunction "1_1") (pintype "passive"))
      (node (ref "R5") (pin "1") (pinfunction "1_1") (pintype "passive"))
      (node (ref "R9") (pin "1") (pinfunction "1_1") (pintype "passive"))
      (node (ref "TPS1") (pin "2") (pinfunction "GND_2") (pintype "passive"))
      (node (ref "U1") (pin "18") (pinfunction "VSS_18") (pintype "power_in"))
      (node (ref "U1") (pin "63") (pinfunction "VSS_63") (pintype "power_in"))
      (node (ref "U2") (pin "1") (pinfunction "GND_1") (pintype "passive"))
      (node (ref "U4") (pin "8") (pinfunction "GND_8") (pintype "passive"))
      (node (ref "U6") (pin "2") (pinfunction "-_2") (pintype "passive"))
      (node (ref "USB1") (pin "1") (pinfunction "SH1_1") (pintype "passive"))
      (node (ref "USB1") (pin "2") (pinfunction "SH2_2") (pintype "passive"))
      (node (ref "USB1") (pin "3") (pinfunction "SH3_3") (pintype "passive"))
      (node (ref "USB1") (pin "4") (pinfunction "SH4_4") (pintype "passive"))
      (node (ref "USB1") (pin "A1") (pinfunction "GND_A1") (pintype "passive"))
      (node (ref "USB1") (pin "A12") (pinfunction "GND_A12") (pintype "passive"))
      (node (ref "USB1") (pin "B1") (pinfunction "GND_B1") (pintype "passive"))
      (node (ref "USB1") (pin "B12") (pinfunction "GND_B12") (pintype "passive"))
      (node (ref "X1") (pin "2") (pinfunction "GND_2") (pintype "passive"))
      (node (ref "XT1") (pin "G") (pintype "passive"))
    )
    (net (code "59") (name "Net-(D1-A)") (class "Default")
      (node (ref "D1") (pin "1") (pinfunction "A_1") (pintype "passive"))
      (node (ref "R1") (pin "1") (pinfunction "1_1") (pintype "passive"))
    )
    (net (code "60") (name "Net-(D2-A)") (class "Default")
      (node (ref "D2") (pin "1") (pinfunction "A_1") (pintype "passive"))
      (node (ref "R2") (pin "1") (pinfunction "1_1") (pintype "passive"))
    )
    (net (code "61") (name "Net-(D3-A)") (class "Default")
      (node (ref "D3") (pin "1") (pinfunction "A_1") (pintype "passive"))
      (node (ref "R12") (pin "2") (pinfunction "2_2") (pintype "passive"))
    )
    (net (code "62") (name "Net-(D4-A)") (class "Default")
      (node (ref "D4") (pin "1") (pinfunction "A_1") (pintype "passive"))
      (node (ref "R10") (pin "1") (pinfunction "1_1") (pintype "passive"))
    )
    (net (code "63") (name "Net-(D5-A)") (class "Default")
      (node (ref "D5") (pin "1") (pinfunction "A_1") (pintype "passive"))
      (node (ref "L2") (pin "1") (pintype "passive"))
      (node (ref "TPS1") (pin "1") (pinfunction "SW_1") (pintype "passive"))
    )
    (net (code "64") (name "Net-(D6-A)") (class "Default")
      (node (ref "D6") (pin "1") (pinfunction "A_1") (pintype "passive"))
      (node (ref "R25") (pin "1") (pinfunction "1_1") (pintype "passive"))
    )
    (net (code "65") (name "Net-(DC1-DCBUS)") (class "Default")
      (node (ref "DC1") (pin "1") (pinfunction "DCBUS_1") (pintype "passive"))
      (node (ref "ON1") (pin "2") (pinfunction "2_2") (pintype "passive"))
    )
    (net (code "66") (name "Net-(OLED1-IM1)") (class "Default")
      (node (ref "OLED1") (pin "5") (pinfunction "IM1_5") (pintype "passive"))
      (node (ref "R29") (pin "1") (pinfunction "1_1") (pintype "passive"))
    )
    (net (code "67") (name "Net-(OLED1-IREF)") (class "Default")
      (node (ref "OLED1") (pin "6") (pinfunction "IREF_6") (pintype "passive"))
      (node (ref "R28") (pin "1") (pinfunction "1_1") (pintype "passive"))
    )
    (net (code "68") (name "Net-(OLED1-RES)") (class "Default")
      (node (ref "OLED1") (pin "8") (pinfunction "RES_8") (pintype "passive"))
      (node (ref "R27") (pin "1") (pinfunction "1_1") (pintype "passive"))
    )
    (net (code "69") (name "Net-(OLED1-VCCOMH)") (class "Default")
      (node (ref "C59") (pin "2") (pinfunction "2_2") (pintype "passive"))
      (node (ref "OLED1") (pin "3") (pinfunction "VCCOMH_3") (pintype "passive"))
    )
    (net (code "70") (name "Net-(Q1-G)") (class "Default")
      (node (ref "Q1") (pin "1") (pinfunction "G_1") (pintype "passive"))
      (node (ref "Q2") (pin "3") (pintype "passive"))
      (node (ref "R5") (pin "2") (pinfunction "2_2") (pintype "passive"))
    )
    (net (code "71") (name "Net-(Q2-Pad2)") (class "Default")
      (node (ref "Q2") (pin "2") (pintype "passive"))
      (node (ref "Q2") (pin "5") (pintype "passive"))
      (node (ref "Q2") (pin "6") (pintype "passive"))
      (node (ref "R3") (pin "1") (pinfunction "1_1") (pintype "passive"))
    )
    (net (code "72") (name "Net-(TPS1-FB)") (class "Default")
      (node (ref "C51") (pin "1") (pinfunction "1_1") (pintype "passive"))
      (node (ref "R26") (pin "1") (pinfunction "1_1") (pintype "passive"))
      (node (ref "R30") (pin "2") (pinfunction "2_2") (pintype "passive"))
      (node (ref "TPS1") (pin "3") (pinfunction "FB_3") (pintype "passive"))
    )
    (net (code "73") (name "Net-(U1A-VCAP_1)") (class "Default")
      (node (ref "C27") (pin "2") (pinfunction "2_2") (pintype "passive"))
      (node (ref "U1") (pin "31") (pinfunction "VCAP_1_31") (pintype "power_in"))
    )
    (net (code "74") (name "Net-(U1A-VCAP_2)") (class "Default")
      (node (ref "C26") (pin "2") (pinfunction "2_2") (pintype "passive"))
      (node (ref "U1") (pin "47") (pinfunction "VCAP_2_47") (pintype "power_in"))
    )
    (net (code "75") (name "Net-(U4-V3)") (class "Default")
      (node (ref "C32") (pin "2") (pinfunction "2_2") (pintype "passive"))
      (node (ref "U4") (pin "5") (pinfunction "V3_5") (pintype "passive"))
    )
    (net (code "76") (name "Net-(U4-X0)") (class "Default")
      (node (ref "C34") (pin "2") (pinfunction "2_2") (pintype "passive"))
      (node (ref "U4") (pin "10") (pinfunction "X0_10") (pintype "passive"))
      (node (ref "XT1") (pin "3") (pintype "passive"))
    )
    (net (code "77") (name "Net-(U4-X1)") (class "Default")
      (node (ref "C33") (pin "2") (pinfunction "2_2") (pintype "passive"))
      (node (ref "U4") (pin "9") (pinfunction "X1_9") (pintype "passive"))
      (node (ref "XT1") (pin "1") (pintype "passive"))
    )
    (net (code "78") (name "PGND") (class "Default")
      (node (ref "C37") (pin "1") (pinfunction "1_1") (pintype "passive"))
      (node (ref "C38") (pin "1") (pinfunction "1_1") (pintype "passive"))
      (node (ref "C39") (pin "1") (pinfunction "1_1") (pintype "passive"))
      (node (ref "C40") (pin "1") (pinfunction "1_1") (pintype "passive"))
      (node (ref "C41") (pin "1") (pinfunction "1_1") (pintype "passive"))
      (node (ref "C42") (pin "1") (pinfunction "1_1") (pintype "passive"))
      (node (ref "C43") (pin "1") (pinfunction "1_1") (pintype "passive"))
      (node (ref "C44") (pin "1") (pinfunction "1_1") (pintype "passive"))
      (node (ref "C45") (pin "1") (pinfunction "1_1") (pintype "passive"))
      (node (ref "C46") (pin "1") (pinfunction "1_1") (pintype "passive"))
      (node (ref "C47") (pin "1") (pinfunction "1_1") (pintype "passive"))
      (node (ref "C48") (pin "1") (pinfunction "1_1") (pintype "passive"))
      (node (ref "C49") (pin "1") (pinfunction "1_1") (pintype "passive"))
      (node (ref "C55") (pin "1") (pinfunction "1_1") (pintype "passive"))
      (node (ref "C56") (pin "1") (pinfunction "1_1") (pintype "passive"))
      (node (ref "C57") (pin "1") (pinfunction "1_1") (pintype "passive"))
      (node (ref "D6") (pin "2") (pinfunction "K_2") (pintype "passive"))
      (node (ref "DC1") (pin "2") (pinfunction "PGND_2") (pintype "passive"))
      (node (ref "L1") (pin "1") (pintype "passive"))
    )
    (net (code "79") (name "USB_5V") (class "Default")
      (node (ref "C10") (pin "2") (pinfunction "2_2") (pintype "passive"))
      (node (ref "C11") (pin "2") (pinfunction "2_2") (pintype "passive"))
      (node (ref "C9") (pin "2") (pinfunction "2_2") (pintype "passive"))
      (node (ref "Q1") (pin "3") (pinfunction "D_3") (pintype "passive"))
      (node (ref "Q2") (pin "1") (pintype "passive"))
      (node (ref "USB1") (pin "A4") (pinfunction "VBUS_A4") (pintype "passive"))
      (node (ref "USB1") (pin "A9") (pinfunction "VBUS_A9") (pintype "passive"))
      (node (ref "USB1") (pin "B4") (pinfunction "VBUS_B4") (pintype "passive"))
      (node (ref "USB1") (pin "B9") (pinfunction "VBUS_B9") (pintype "passive"))
    )
    (net (code "80") (name "VCC") (class "Default")
      (node (ref "C1") (pin "2") (pinfunction "2_2") (pintype "passive"))
      (node (ref "C2") (pin "2") (pinfunction "2_2") (pintype "passive"))
      (node (ref "C29") (pin "2") (pinfunction "2_2") (pintype "passive"))
      (node (ref "C3") (pin "2") (pinfunction "2_2") (pintype "passive"))
      (node (ref "C30") (pin "2") (pinfunction "2_2") (pintype "passive"))
      (node (ref "C31") (pin "2") (pinfunction "2_2") (pintype "passive"))
      (node (ref "C4") (pin "2") (pinfunction "2_2") (pintype "passive"))
      (node (ref "C58") (pin "2") (pinfunction "2_2") (pintype "passive"))
      (node (ref "C6") (pin "2") (pinfunction "2_2") (pintype "passive"))
      (node (ref "C7") (pin "2") (pinfunction "2_2") (pintype "passive"))
      (node (ref "C8") (pin "2") (pinfunction "2_2") (pintype "passive"))
      (node (ref "J1") (pin "5") (pinfunction "5_5") (pintype "passive"))
      (node (ref "OLED1") (pin "4") (pinfunction "VDD_4") (pintype "passive"))
      (node (ref "R14") (pin "2") (pinfunction "2_2") (pintype "passive"))
      (node (ref "R15") (pin "2") (pinfunction "2_2") (pintype "passive"))
      (node (ref "R16") (pin "2") (pinfunction "2_2") (pintype "passive"))
      (node (ref "R18") (pin "2") (pinfunction "2_2") (pintype "passive"))
      (node (ref "R19") (pin "2") (pinfunction "2_2") (pintype "passive"))
      (node (ref "R2") (pin "2") (pinfunction "2_2") (pintype "passive"))
      (node (ref "R20") (pin "2") (pinfunction "2_2") (pintype "passive"))
      (node (ref "R23") (pin "2") (pinfunction "2_2") (pintype "passive"))
      (node (ref "R24") (pin "2") (pinfunction "2_2") (pintype "passive"))
      (node (ref "R27") (pin "2") (pinfunction "2_2") (pintype "passive"))
      (node (ref "R29") (pin "2") (pinfunction "2_2") (pintype "passive"))
      (node (ref "R6") (pin "1") (pinfunction "1_1") (pintype "passive"))
      (node (ref "R7") (pin "1") (pinfunction "1_1") (pintype "passive"))
      (node (ref "R8") (pin "1") (pinfunction "1_1") (pintype "passive"))
      (node (ref "TP1") (pin "1") (pintype "passive"))
      (node (ref "U1") (pin "1") (pinfunction "VBAT_1") (pintype "power_in"))
      (node (ref "U1") (pin "19") (pinfunction "VDD_19") (pintype "power_in"))
      (node (ref "U1") (pin "32") (pinfunction "VDD_32") (pintype "power_in"))
      (node (ref "U1") (pin "48") (pinfunction "VDD_48") (pintype "power_in"))
      (node (ref "U1") (pin "64") (pinfunction "VDD_64") (pintype "power_in"))
      (node (ref "U2") (pin "2") (pinfunction "Vout_2") (pintype "passive"))
      (node (ref "U2") (pin "4") (pinfunction "Vout_(tab)_4") (pintype "passive"))
      (node (ref "U4") (pin "19") (pinfunction "VCC_19") (pintype "passive"))
    )
    (net (code "81") (name "unconnected-(OLED1-NC1-Pad1)") (class "Default")
      (node (ref "OLED1") (pin "1") (pinfunction "NC1_1") (pintype "passive"))
    )
    (net (code "82") (name "unconnected-(OLED1-NC2-Pad13)") (class "Default")
      (node (ref "OLED1") (pin "13") (pinfunction "NC2_13") (pintype "passive"))
    )
    (net (code "83") (name "unconnected-(ON1-Pad1)") (class "Default")
      (node (ref "ON1") (pin "1") (pinfunction "1_1") (pintype "passive"))
    )
    (net (code "84") (name "unconnected-(ON1-PadEH)") (class "Default")
      (node (ref "ON1") (pin "EH") (pinfunction "EH_EH") (pintype "passive"))
    )
    (net (code "85") (name "unconnected-(U1A-PA4-Pad20)") (class "Default")
      (node (ref "U1") (pin "20") (pinfunction "PA4_20") (pintype "bidirectional"))
    )
    (net (code "86") (name "unconnected-(U1A-PB8-Pad61)") (class "Default")
      (node (ref "U1") (pin "61") (pinfunction "PB8_61") (pintype "bidirectional"))
    )
    (net (code "87") (name "unconnected-(U1A-PB9-Pad62)") (class "Default")
      (node (ref "U1") (pin "62") (pinfunction "PB9_62") (pintype "bidirectional"))
    )
    (net (code "88") (name "unconnected-(U1A-PC5-Pad25)") (class "Default")
      (node (ref "U1") (pin "25") (pinfunction "PC5_25") (pintype "bidirectional"))
    )
    (net (code "89") (name "unconnected-(U4-ACT#-Pad2)") (class "Default")
      (node (ref "U4") (pin "2") (pinfunction "ACT#_2") (pintype "passive"))
    )
    (net (code "90") (name "unconnected-(U4-CKO-Pad1)") (class "Default")
      (node (ref "U4") (pin "1") (pinfunction "CKO_1") (pintype "passive"))
    )
    (net (code "91") (name "unconnected-(U4-CTS#-Pad11)") (class "Default")
      (node (ref "U4") (pin "11") (pinfunction "CTS#_11") (pintype "passive"))
    )
    (net (code "92") (name "unconnected-(U4-DCD#-Pad14)") (class "Default")
      (node (ref "U4") (pin "14") (pinfunction "DCD#_14") (pintype "passive"))
    )
    (net (code "93") (name "unconnected-(U4-DSR#-Pad12)") (class "Default")
      (node (ref "U4") (pin "12") (pinfunction "DSR#_12") (pintype "passive"))
    )
    (net (code "94") (name "unconnected-(U4-DTR#-Pad15)") (class "Default")
      (node (ref "U4") (pin "15") (pinfunction "DTR#_15") (pintype "passive"))
    )
    (net (code "95") (name "unconnected-(U4-NC-Pad17)") (class "Default")
      (node (ref "U4") (pin "17") (pinfunction "NC_17") (pintype "passive"))
    )
    (net (code "96") (name "unconnected-(U4-NOS#-Pad20)") (class "Default")
      (node (ref "U4") (pin "20") (pinfunction "NOS#_20") (pintype "passive"))
    )
    (net (code "97") (name "unconnected-(U4-R232-Pad18)") (class "Default")
      (node (ref "U4") (pin "18") (pinfunction "R232_18") (pintype "passive"))
    )
    (net (code "98") (name "unconnected-(U4-RI#-Pad13)") (class "Default")
      (node (ref "U4") (pin "13") (pinfunction "RI#_13") (pintype "passive"))
    )
    (net (code "99") (name "unconnected-(U4-RTS#-Pad16)") (class "Default")
      (node (ref "U4") (pin "16") (pinfunction "RTS#_16") (pintype "passive"))
    )
    (net (code "100") (name "unconnected-(USB1-CC1-PadA5)") (class "Default")
      (node (ref "USB1") (pin "A5") (pinfunction "CC1_A5") (pintype "passive"))
    )
    (net (code "101") (name "unconnected-(USB1-CC2-PadB5)") (class "Default")
      (node (ref "USB1") (pin "B5") (pinfunction "CC2_B5") (pintype "passive"))
    )
    (net (code "102") (name "unconnected-(USB1-RX1+-PadB11)") (class "Default")
      (node (ref "USB1") (pin "B11") (pinfunction "RX1+_B11") (pintype "passive"))
    )
    (net (code "103") (name "unconnected-(USB1-RX1--PadB10)") (class "Default")
      (node (ref "USB1") (pin "B10") (pinfunction "RX1-_B10") (pintype "passive"))
    )
    (net (code "104") (name "unconnected-(USB1-RX2+-PadA11)") (class "Default")
      (node (ref "USB1") (pin "A11") (pinfunction "RX2+_A11") (pintype "passive"))
    )
    (net (code "105") (name "unconnected-(USB1-RX2--PadA10)") (class "Default")
      (node (ref "USB1") (pin "A10") (pinfunction "RX2-_A10") (pintype "passive"))
    )
    (net (code "106") (name "unconnected-(USB1-SBU1-PadA8)") (class "Default")
      (node (ref "USB1") (pin "A8") (pinfunction "SBU1_A8") (pintype "passive"))
    )
    (net (code "107") (name "unconnected-(USB1-SBU2-PadB8)") (class "Default")
      (node (ref "USB1") (pin "B8") (pinfunction "SBU2_B8") (pintype "passive"))
    )
    (net (code "108") (name "unconnected-(USB1-TX1+-PadA2)") (class "Default")
      (node (ref "USB1") (pin "A2") (pinfunction "TX1+_A2") (pintype "passive"))
    )
    (net (code "109") (name "unconnected-(USB1-TX1--PadA3)") (class "Default")
      (node (ref "USB1") (pin "A3") (pinfunction "TX1-_A3") (pintype "passive"))
    )
    (net (code "110") (name "unconnected-(USB1-TX2+-PadB2)") (class "Default")
      (node (ref "USB1") (pin "B2") (pinfunction "TX2+_B2") (pintype "passive"))
    )
    (net (code "111") (name "unconnected-(USB1-TX2--PadB3)") (class "Default")
      (node (ref "USB1") (pin "B3") (pinfunction "TX2-_B3") (pintype "passive"))
    )
  )
)
